# RGB_SL.net
KiCad netlist of a schematic drawn in Altium Designer
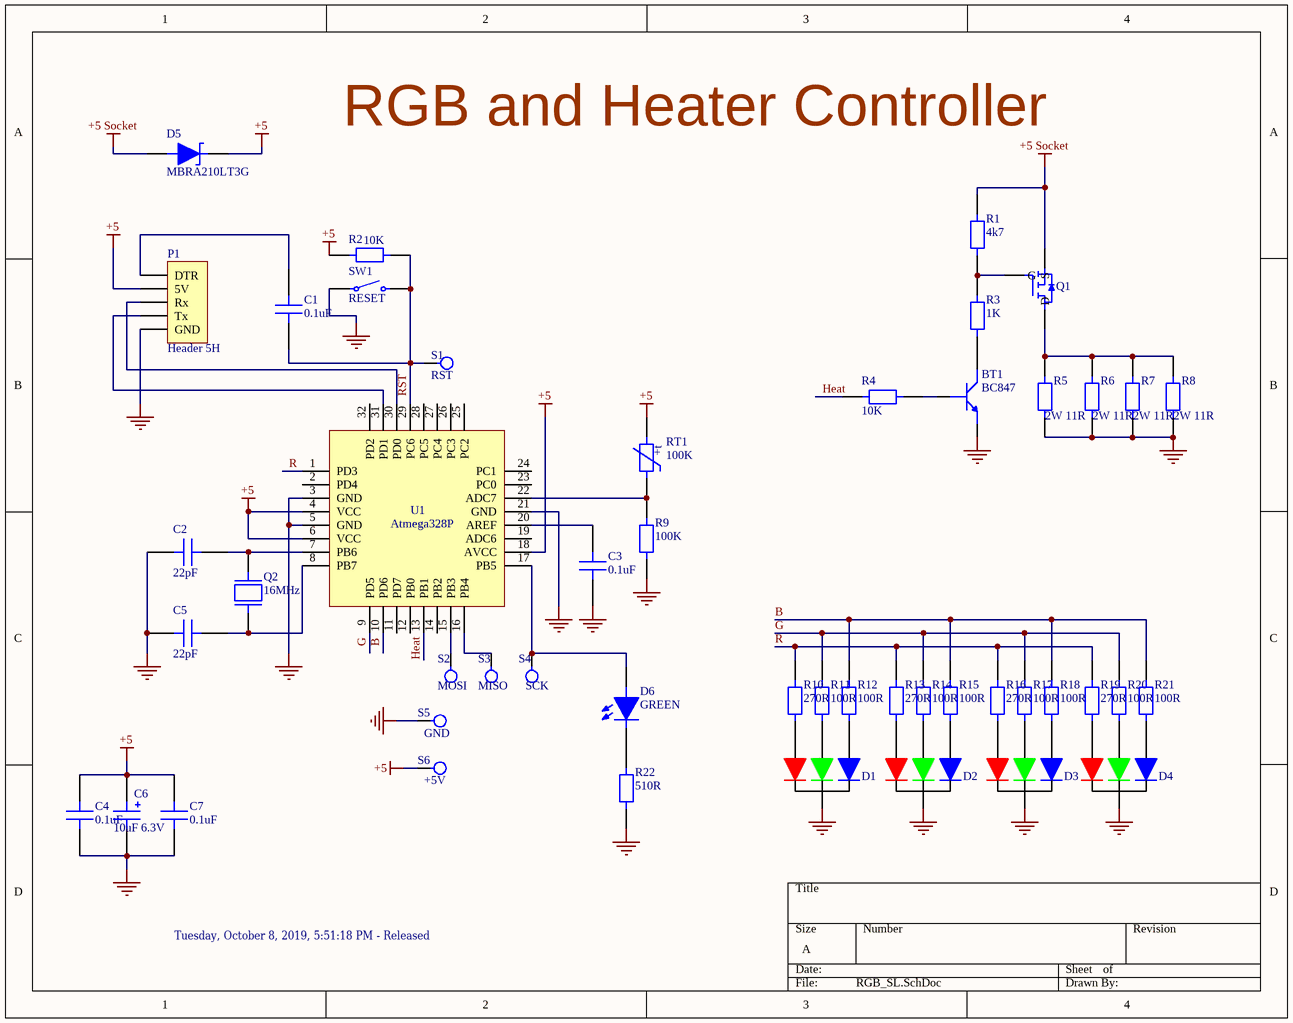
[diagram p0: RGB_SL.SchDoc]

(export (version "E")
  (design (tool "Eeschema 10.0.6"))
  (components
    (comp (ref "BT1")
      (value "BC847")
      (footprint "SOT95P240X100-3M")
      (description "Trans NPN 45V 0.1A Automotive 3-Pin SOT-23 T/R GP BJT")
      (fields
        (field (name "MANUFACTURER") "Infineon")
        (field (name "MANUFACTURER PART NUMBER") "BC847AE6327")
      )
      (libsource (lib "MainBLib") (part "BC847AE6327"))
    )
    (comp (ref "C1")
      (value "0.1uF")
      (footprint "0805 Ceramic Capacitor")
      (description "Ceramic Cap 0.1uF 50 V 10% MLCC - SMD/SMT")
      (fields
        (field (name "MANUFACTURER") "Vishay Vitramon")
        (field (name "MANUFACTURER PART NUMBER") "VJ0805Y104KXAAT")
      )
      (libsource (lib "MainBLib") (part "VJ0805Y104KXAAT"))
    )
    (comp (ref "C2")
      (value "22pF")
      (footprint "0805 Ceramic Capacitor")
      (description "Ceramic Cap 22 pF 50 V ±5 % Tolerance C0G/NP0 SMT Multilayer")
      (fields
        (field (name "MANUFACTURER") "Vishay")
        (field (name "MANUFACTURER PART NUMBER") "VJ0805A220JXACW1BC")
      )
      (libsource (lib "MainBLib") (part "VJ0805A220JXACW1BC"))
    )
    (comp (ref "C3")
      (value "0.1uF")
      (footprint "0805 Ceramic Capacitor")
      (description "Ceramic Cap 0.1uF 50 V 10% MLCC - SMD/SMT")
      (fields
        (field (name "MANUFACTURER") "Vishay Vitramon")
        (field (name "MANUFACTURER PART NUMBER") "VJ0805Y104KXAAT")
      )
      (libsource (lib "MainBLib") (part "VJ0805Y104KXAAT"))
    )
    (comp (ref "C4")
      (value "0.1uF")
      (footprint "0805 Ceramic Capacitor")
      (description "Ceramic Cap 0.1uF 50 V 10% MLCC - SMD/SMT")
      (fields
        (field (name "MANUFACTURER") "Vishay Vitramon")
        (field (name "MANUFACTURER PART NUMBER") "VJ0805Y104KXAAT")
      )
      (libsource (lib "MainBLib") (part "VJ0805Y104KXAAT"))
    )
    (comp (ref "C5")
      (value "22pF")
      (footprint "0805 Ceramic Capacitor")
      (description "Ceramic Cap 22 pF 50 V ±5 % Tolerance C0G/NP0 SMT Multilayer")
      (fields
        (field (name "MANUFACTURER") "Vishay")
        (field (name "MANUFACTURER PART NUMBER") "VJ0805A220JXACW1BC")
      )
      (libsource (lib "MainBLib") (part "VJ0805A220JXACW1BC"))
    )
    (comp (ref "C6")
      (value "10uF 6.3V")
      (footprint "CAP MP3216X16M")
      (description "CAP TANT 10UF 6.3V 10% 1206")
      (fields
        (field (name "MANUFACTURER") "Vishay Sprague")
        (field (name "MANUFACTURER PART NUMBER") "293D106X96R3A2TE3")
      )
      (libsource (lib "MainBLib") (part "293D106X96R3A2TE3"))
    )
    (comp (ref "C7")
      (value "0.1uF")
      (footprint "0805 Ceramic Capacitor")
      (description "Ceramic Cap 0.1uF 50 V 10% MLCC - SMD/SMT")
      (fields
        (field (name "MANUFACTURER") "Vishay Vitramon")
        (field (name "MANUFACTURER PART NUMBER") "VJ0805Y104KXAAT")
      )
      (libsource (lib "MainBLib") (part "VJ0805Y104KXAAT"))
    )
    (comp (ref "D1")
      (value "LED RGB")
      (footprint "LED RGB")
      (description "LED RGB DIFFUSED 5MM T/H")
      (fields (field (name "MANUFACTURER") "Inolux") (field (name "MANUFACTURER PART NUMBER") "HV-5RGB25"))
      (libsource (lib "MainBLib") (part "HV-5RGB25"))
    )
    (comp (ref "D2")
      (value "LED RGB")
      (footprint "LED RGB")
      (description "LED RGB DIFFUSED 5MM T/H")
      (fields (field (name "MANUFACTURER") "Inolux") (field (name "MANUFACTURER PART NUMBER") "HV-5RGB25"))
      (libsource (lib "MainBLib") (part "HV-5RGB25"))
    )
    (comp (ref "D3")
      (value "LED RGB")
      (footprint "LED RGB")
      (description "LED RGB DIFFUSED 5MM T/H")
      (fields (field (name "MANUFACTURER") "Inolux") (field (name "MANUFACTURER PART NUMBER") "HV-5RGB25"))
      (libsource (lib "MainBLib") (part "HV-5RGB25"))
    )
    (comp (ref "D4")
      (value "LED RGB")
      (footprint "LED RGB")
      (description "LED RGB DIFFUSED 5MM T/H")
      (fields (field (name "MANUFACTURER") "Inolux") (field (name "MANUFACTURER PART NUMBER") "HV-5RGB25"))
      (libsource (lib "MainBLib") (part "HV-5RGB25"))
    )
    (comp (ref "D5")
      (value "MBRA210LT3G")
      (footprint "DIOM4326X22M")
      (description "DIODE SCHOTTKY 10V 2A SMA")
      (fields (field (name "MANUFACTURER") "ON Semiconductor"))
      (libsource (lib "MainBLib") (part "MBRA210LT3G"))
    )
    (comp (ref "D6")
      (value "GREEN")
      (footprint "Led G")
      (description "LED GREEN DIFFUSED 0805 SMD")
      (fields
        (field (name "MANUFACTURER") "VCC CHML")
        (field (name "MANUFACTURER PART NUMBER") "CMD17-21VGD/TR8")
      )
      (libsource (lib "MainBLib") (part "CMD17-21VGD/TR8"))
    )
    (comp (ref "P1")
      (value "Header 5H")
      (footprint "HDR1X5H")
      (description "Header, 5-Pin, Right Angle")
      (fields (field (name "PUBLISHER") "Altium Limited"))
      (libsource (lib "Miscellaneous Connectors") (part "Header 5H"))
    )
    (comp (ref "Q1")
      (value "MOSFET P-Ch")
      (footprint "DPAK254P1524X483-3M")
      (description "MOSFET P-Ch LL FET Enhancement Mode")
      (fields
        (field (name "MANUFACTURER") "ON Semiconductor / Fairchild")
        (field (name "MANUFACTURER PART NUMBER") "NDP6020P")
      )
      (libsource (lib "MainBLib") (part "NDP6020P"))
    )
    (comp (ref "Q2")
      (value "16MHz")
      (footprint "Crystal")
      (description "CRYSTAL 16.0000MHZ 20PF SMD")
      (fields
        (field (name "MANUFACTURER") "ECS International")
        (field (name "MANUFACTURER PART NUMBER") "ECS-160-20-5PX-TR")
      )
      (libsource (lib "MainBLib") (part "ECS-160-20-5PX-TR"))
    )
    (comp (ref "R1")
      (value "4k7")
      (footprint "0805 Res")
      (description "RES SMD 4.7K Ohm 5% 1/8W ±200ppm/°C Molded SMD Paper T/R")
      (fields
        (field (name "MANUFACTURER") "Vishay")
        (field (name "MANUFACTURER PART NUMBER") "CRCW08054K70JNEAC")
      )
      (libsource (lib "MainBLib") (part "CRCW08054K70JNEAC"))
    )
    (comp (ref "R2")
      (value "10K")
      (footprint "0805 Res")
      (description "RES SMD 10K OHM 1% 1/8W 0805")
      (fields
        (field (name "MANUFACTURER") "Vishay Dale")
        (field (name "MANUFACTURER PART NUMBER") "CRCW080510K0FKTA")
      )
      (libsource (lib "MainBLib") (part "CRCW080510K0FKTA"))
    )
    (comp (ref "R3")
      (value "1K")
      (footprint "0805 Res")
      (description "RES SMD 1K OHM 1% 1/8W 0805")
      (fields
        (field (name "MANUFACTURER") "Vishay Dale")
        (field (name "MANUFACTURER PART NUMBER") "CRCW08051K00FKEA")
      )
      (libsource (lib "MainBLib") (part "CRCW08051K00FKEA"))
    )
    (comp (ref "R4")
      (value "10K")
      (footprint "0805 Res")
      (description "RES SMD 10K OHM 1% 1/8W 0805")
      (fields
        (field (name "MANUFACTURER") "Vishay Dale")
        (field (name "MANUFACTURER PART NUMBER") "CRCW080510K0FKTA")
      )
      (libsource (lib "MainBLib") (part "CRCW080510K0FKTA"))
    )
    (comp (ref "R5")
      (value "2W 11R")
      (footprint "RES T/H 2W")
      (description "RES T/H 11 Ohm 2W 5% ±300ppm/°C Conformal AXL Thru-Hole Ammo Pack")
      (fields
        (field (name "MANUFACTURER") "TE Connectivity")
        (field (name "MANUFACTURER PART NUMBER") "RR02J11RTB")
      )
      (libsource (lib "MainBLib") (part "RR02J11RTB"))
    )
    (comp (ref "R6")
      (value "2W 11R")
      (footprint "RES T/H 2W")
      (description "RES T/H 11 Ohm 2W 5% ±300ppm/°C Conformal AXL Thru-Hole Ammo Pack")
      (fields
        (field (name "MANUFACTURER") "TE Connectivity")
        (field (name "MANUFACTURER PART NUMBER") "RR02J11RTB")
      )
      (libsource (lib "MainBLib") (part "RR02J11RTB"))
    )
    (comp (ref "R7")
      (value "2W 11R")
      (footprint "RES T/H 2W")
      (description "RES T/H 11 Ohm 2W 5% ±300ppm/°C Conformal AXL Thru-Hole Ammo Pack")
      (fields
        (field (name "MANUFACTURER") "TE Connectivity")
        (field (name "MANUFACTURER PART NUMBER") "RR02J11RTB")
      )
      (libsource (lib "MainBLib") (part "RR02J11RTB"))
    )
    (comp (ref "R8")
      (value "2W 11R")
      (footprint "RES T/H 2W")
      (description "RES T/H 11 Ohm 2W 5% ±300ppm/°C Conformal AXL Thru-Hole Ammo Pack")
      (fields
        (field (name "MANUFACTURER") "TE Connectivity")
        (field (name "MANUFACTURER PART NUMBER") "RR02J11RTB")
      )
      (libsource (lib "MainBLib") (part "RR02J11RTB"))
    )
    (comp (ref "R9")
      (value "100K")
      (footprint "0805 Res")
      (fields
        (field (name "MANUFACTURER") "Vishay")
        (field (name "MANUFACTURER PART NUMBER") "TNPW0805100KFEEA")
        (field (name "TOLERANCE") "1%")
      )
      (libsource (lib "MainBLib") (part "TNPW0805100KFEEA"))
    )
    (comp (ref "R10")
      (value "270R")
      (footprint "1206 RES")
      (description "RES SMD 270 OHM 1% 1/4W 1206")
      (fields
        (field (name "MANUFACTURER") "Vishay Semiconductors")
        (field (name "MANUFACTURER PART NUMBER") "CRCW1206270RFKEAC")
      )
      (libsource (lib "MainBLib") (part "CRCW1206270RFKEAC"))
    )
    (comp (ref "R11")
      (value "100R")
      (footprint "1206 RES")
      (description "RES SMD 100 OHM 1% 1/4W 1206")
      (fields
        (field (name "MANUFACTURER") "Vishay Semiconductors")
        (field (name "MANUFACTURER PART NUMBER") "CRCW1206100RFKEAC")
      )
      (libsource (lib "MainBLib") (part "CRCW1206100RFKEAC"))
    )
    (comp (ref "R12")
      (value "100R")
      (footprint "1206 RES")
      (description "RES SMD 100 OHM 1% 1/4W 1206")
      (fields
        (field (name "MANUFACTURER") "Vishay Semiconductors")
        (field (name "MANUFACTURER PART NUMBER") "CRCW1206100RFKEAC")
      )
      (libsource (lib "MainBLib") (part "CRCW1206100RFKEAC"))
    )
    (comp (ref "R13")
      (value "270R")
      (footprint "1206 RES")
      (description "RES SMD 270 OHM 1% 1/4W 1206")
      (fields
        (field (name "MANUFACTURER") "Vishay Semiconductors")
        (field (name "MANUFACTURER PART NUMBER") "CRCW1206270RFKEAC")
      )
      (libsource (lib "MainBLib") (part "CRCW1206270RFKEAC"))
    )
    (comp (ref "R14")
      (value "100R")
      (footprint "1206 RES")
      (description "RES SMD 100 OHM 1% 1/4W 1206")
      (fields
        (field (name "MANUFACTURER") "Vishay Semiconductors")
        (field (name "MANUFACTURER PART NUMBER") "CRCW1206100RFKEAC")
      )
      (libsource (lib "MainBLib") (part "CRCW1206100RFKEAC"))
    )
    (comp (ref "R15")
      (value "100R")
      (footprint "1206 RES")
      (description "RES SMD 100 OHM 1% 1/4W 1206")
      (fields
        (field (name "MANUFACTURER") "Vishay Semiconductors")
        (field (name "MANUFACTURER PART NUMBER") "CRCW1206100RFKEAC")
      )
      (libsource (lib "MainBLib") (part "CRCW1206100RFKEAC"))
    )
    (comp (ref "R16")
      (value "270R")
      (footprint "1206 RES")
      (description "RES SMD 270 OHM 1% 1/4W 1206")
      (fields
        (field (name "MANUFACTURER") "Vishay Semiconductors")
        (field (name "MANUFACTURER PART NUMBER") "CRCW1206270RFKEAC")
      )
      (libsource (lib "MainBLib") (part "CRCW1206270RFKEAC"))
    )
    (comp (ref "R17")
      (value "100R")
      (footprint "1206 RES")
      (description "RES SMD 100 OHM 1% 1/4W 1206")
      (fields
        (field (name "MANUFACTURER") "Vishay Semiconductors")
        (field (name "MANUFACTURER PART NUMBER") "CRCW1206100RFKEAC")
      )
      (libsource (lib "MainBLib") (part "CRCW1206100RFKEAC"))
    )
    (comp (ref "R18")
      (value "100R")
      (footprint "1206 RES")
      (description "RES SMD 100 OHM 1% 1/4W 1206")
      (fields
        (field (name "MANUFACTURER") "Vishay Semiconductors")
        (field (name "MANUFACTURER PART NUMBER") "CRCW1206100RFKEAC")
      )
      (libsource (lib "MainBLib") (part "CRCW1206100RFKEAC"))
    )
    (comp (ref "R19")
      (value "270R")
      (footprint "1206 RES")
      (description "RES SMD 270 OHM 1% 1/4W 1206")
      (fields
        (field (name "MANUFACTURER") "Vishay Semiconductors")
        (field (name "MANUFACTURER PART NUMBER") "CRCW1206270RFKEAC")
      )
      (libsource (lib "MainBLib") (part "CRCW1206270RFKEAC"))
    )
    (comp (ref "R20")
      (value "100R")
      (footprint "1206 RES")
      (description "RES SMD 100 OHM 1% 1/4W 1206")
      (fields
        (field (name "MANUFACTURER") "Vishay Semiconductors")
        (field (name "MANUFACTURER PART NUMBER") "CRCW1206100RFKEAC")
      )
      (libsource (lib "MainBLib") (part "CRCW1206100RFKEAC"))
    )
    (comp (ref "R21")
      (value "100R")
      (footprint "1206 RES")
      (description "RES SMD 100 OHM 1% 1/4W 1206")
      (fields
        (field (name "MANUFACTURER") "Vishay Semiconductors")
        (field (name "MANUFACTURER PART NUMBER") "CRCW1206100RFKEAC")
      )
      (libsource (lib "MainBLib") (part "CRCW1206100RFKEAC"))
    )
    (comp (ref "R22")
      (value "510R")
      (footprint "0805 Res")
      (description "RES SMD 510 OHM 1% 1/8W 0805")
      (fields
        (field (name "MANUFACTURER") "Vishay")
        (field (name "MANUFACTURER PART NUMBER") "CRCW0805510RFKEA")
      )
      (libsource (lib "MainBLib") (part "CRCW0805510RFKEA"))
    )
    (comp (ref "RT1")
      (value "100K")
      (footprint "THERMISTOR")
      (description "THERMISTOR 100K OHM 5% BEAD")
      (fields
        (field (name "MANUFACTURER") "Canadian Thermostats")
        (field (name "MANUFACTURER PART NUMBER") "MF52A1104J3950")
      )
      (libsource (lib "MainBLib") (part "MF52A1104J3950"))
    )
    (comp (ref "S1") (value "RST") (footprint "Test Pad") (libsource (lib "MainBLib") (part "Test Pad")))
    (comp (ref "S2") (value "MOSI") (footprint "Test Pad") (libsource (lib "MainBLib") (part "Test Pad")))
    (comp (ref "S3") (value "MISO") (footprint "Test Pad") (libsource (lib "MainBLib") (part "Test Pad")))
    (comp (ref "S4") (value "SCK") (footprint "Test Pad") (libsource (lib "MainBLib") (part "Test Pad")))
    (comp (ref "S5") (value "GND") (footprint "Test Pad") (libsource (lib "MainBLib") (part "Test Pad")))
    (comp (ref "S6") (value "+5V") (footprint "Test Pad") (libsource (lib "MainBLib") (part "Test Pad")))
    (comp (ref "SW1")
      (value "RESET")
      (footprint "SWITCH")
      (description "SWITCH TACTILE SPST-NO 0.05A 24V")
      (fields
        (field (name "MANUFACTURER") "TE Connectivity")
        (field (name "MANUFACTURER PART NUMBER") "FSMSMTR")
      )
      (libsource (lib "MainBLib") (part "FSMSMTR"))
    )
    (comp (ref "U1")
      (value "Atmega328P")
      (footprint "TQFP80P900X900X120-32M")
      (description "IC MCU 8BIT 32KB FLASH 32TQFP")
      (fields
        (field (name "MANUFACTURER") "Microchip")
        (field (name "MANUFACTURER PART NUMBER") "ATMEGA328P-AUR")
      )
      (libsource (lib "MainBLib") (part "ATMEGA328P-AUR"))
    )
  )
  (nets
    (net (code "1") (name "+5") (class "Default")
      (node (ref "C4") (pin "2") (pinfunction "2_2") (pintype "passive"))
      (node (ref "C6") (pin "1") (pinfunction "1_1") (pintype "passive"))
      (node (ref "C7") (pin "2") (pinfunction "2_2") (pintype "passive"))
      (node (ref "D5") (pin "1") (pinfunction "1_1") (pintype "passive"))
      (node (ref "P1") (pin "2") (pinfunction "5V_2") (pintype "passive"))
      (node (ref "R2") (pin "1") (pinfunction "1_1") (pintype "passive"))
      (node (ref "RT1") (pin "2") (pinfunction "2_2") (pintype "passive"))
      (node (ref "S6") (pin "1") (pinfunction "1_1") (pintype "passive"))
      (node (ref "U1") (pin "18") (pinfunction "AVCC_18") (pintype "passive"))
      (node (ref "U1") (pin "4") (pinfunction "VCC_4") (pintype "passive"))
      (node (ref "U1") (pin "6") (pinfunction "VCC_6") (pintype "passive"))
    )
    (net (code "2") (name "+5 Socket") (class "Default")
      (node (ref "D5") (pin "2") (pinfunction "2_2") (pintype "passive"))
      (node (ref "Q1") (pin "3") (pinfunction "S_3") (pintype "passive"))
      (node (ref "R1") (pin "2") (pinfunction "2_2") (pintype "passive"))
    )
    (net (code "3") (name "/B") (class "Default")
      (node (ref "R12") (pin "2") (pinfunction "2_2") (pintype "passive"))
      (node (ref "R15") (pin "2") (pinfunction "2_2") (pintype "passive"))
      (node (ref "R18") (pin "2") (pinfunction "2_2") (pintype "passive"))
      (node (ref "R21") (pin "2") (pinfunction "2_2") (pintype "passive"))
      (node (ref "U1") (pin "10") (pinfunction "PD6_10") (pintype "passive"))
    )
    (net (code "4") (name "/G") (class "Default")
      (node (ref "R11") (pin "2") (pinfunction "2_2") (pintype "passive"))
      (node (ref "R14") (pin "2") (pinfunction "2_2") (pintype "passive"))
      (node (ref "R17") (pin "2") (pinfunction "2_2") (pintype "passive"))
      (node (ref "R20") (pin "2") (pinfunction "2_2") (pintype "passive"))
      (node (ref "U1") (pin "9") (pinfunction "PD5_9") (pintype "passive"))
    )
    (net (code "5") (name "/Heat") (class "Default")
      (node (ref "R4") (pin "1") (pinfunction "1_1") (pintype "passive"))
      (node (ref "U1") (pin "13") (pinfunction "PB1_13") (pintype "passive"))
    )
    (net (code "6") (name "/R") (class "Default")
      (node (ref "R10") (pin "2") (pinfunction "2_2") (pintype "passive"))
      (node (ref "R13") (pin "2") (pinfunction "2_2") (pintype "passive"))
      (node (ref "R16") (pin "2") (pinfunction "2_2") (pintype "passive"))
      (node (ref "R19") (pin "2") (pinfunction "2_2") (pintype "passive"))
      (node (ref "U1") (pin "1") (pinfunction "PD3_1") (pintype "passive"))
    )
    (net (code "7") (name "/RST") (class "Default")
      (node (ref "C1") (pin "1") (pinfunction "1_1") (pintype "passive"))
      (node (ref "R2") (pin "2") (pinfunction "2_2") (pintype "passive"))
      (node (ref "S1") (pin "1") (pinfunction "1_1") (pintype "passive"))
      (node (ref "SW1") (pin "2") (pinfunction "2_2") (pintype "passive"))
      (node (ref "U1") (pin "29") (pinfunction "PC6_29") (pintype "passive"))
    )
    (net (code "8") (name "GND") (class "Default")
      (node (ref "BT1") (pin "2") (pinfunction "2_2") (pintype "passive"))
      (node (ref "C2") (pin "1") (pinfunction "1_1") (pintype "passive"))
      (node (ref "C3") (pin "1") (pinfunction "1_1") (pintype "passive"))
      (node (ref "C4") (pin "1") (pinfunction "1_1") (pintype "passive"))
      (node (ref "C5") (pin "1") (pinfunction "1_1") (pintype "passive"))
      (node (ref "C6") (pin "2") (pinfunction "2_2") (pintype "passive"))
      (node (ref "C7") (pin "1") (pinfunction "1_1") (pintype "passive"))
      (node (ref "D1") (pin "3") (pinfunction "3_3") (pintype "passive"))
      (node (ref "D2") (pin "3") (pinfunction "3_3") (pintype "passive"))
      (node (ref "D3") (pin "3") (pinfunction "3_3") (pintype "passive"))
      (node (ref "D4") (pin "3") (pinfunction "3_3") (pintype "passive"))
      (node (ref "P1") (pin "5") (pinfunction "GND_5") (pintype "passive"))
      (node (ref "R22") (pin "1") (pinfunction "1_1") (pintype "passive"))
      (node (ref "R5") (pin "1") (pinfunction "1_1") (pintype "passive"))
      (node (ref "R6") (pin "1") (pinfunction "1_1") (pintype "passive"))
      (node (ref "R7") (pin "1") (pinfunction "1_1") (pintype "passive"))
      (node (ref "R8") (pin "1") (pinfunction "1_1") (pintype "passive"))
      (node (ref "R9") (pin "1") (pinfunction "1_1") (pintype "passive"))
      (node (ref "S5") (pin "1") (pinfunction "1_1") (pintype "passive"))
      (node (ref "SW1") (pin "1") (pinfunction "1_1") (pintype "passive"))
      (node (ref "U1") (pin "21") (pinfunction "GND_21") (pintype "passive"))
      (node (ref "U1") (pin "3") (pinfunction "GND_3") (pintype "passive"))
      (node (ref "U1") (pin "5") (pinfunction "GND_5") (pintype "passive"))
    )
    (net (code "9") (name "Net-(BT1-Pad1)") (class "Default")
      (node (ref "BT1") (pin "1") (pinfunction "1_1") (pintype "passive"))
      (node (ref "R4") (pin "2") (pinfunction "2_2") (pintype "passive"))
    )
    (net (code "10") (name "Net-(BT1-Pad3)") (class "Default")
      (node (ref "BT1") (pin "3") (pinfunction "3_3") (pintype "passive"))
      (node (ref "R3") (pin "1") (pinfunction "1_1") (pintype "passive"))
    )
    (net (code "11") (name "Net-(D1-B)") (class "Default")
      (node (ref "D1") (pin "1") (pinfunction "B_1") (pintype "passive"))
      (node (ref "R12") (pin "1") (pinfunction "1_1") (pintype "passive"))
    )
    (net (code "12") (name "Net-(D1-G)") (class "Default")
      (node (ref "D1") (pin "4") (pinfunction "G_4") (pintype "passive"))
      (node (ref "R11") (pin "1") (pinfunction "1_1") (pintype "passive"))
    )
    (net (code "13") (name "Net-(D1-R)") (class "Default")
      (node (ref "D1") (pin "2") (pinfunction "R_2") (pintype "passive"))
      (node (ref "R10") (pin "1") (pinfunction "1_1") (pintype "passive"))
    )
    (net (code "14") (name "Net-(D2-B)") (class "Default")
      (node (ref "D2") (pin "1") (pinfunction "B_1") (pintype "passive"))
      (node (ref "R15") (pin "1") (pinfunction "1_1") (pintype "passive"))
    )
    (net (code "15") (name "Net-(D2-G)") (class "Default")
      (node (ref "D2") (pin "4") (pinfunction "G_4") (pintype "passive"))
      (node (ref "R14") (pin "1") (pinfunction "1_1") (pintype "passive"))
    )
    (net (code "16") (name "Net-(D2-R)") (class "Default")
      (node (ref "D2") (pin "2") (pinfunction "R_2") (pintype "passive"))
      (node (ref "R13") (pin "1") (pinfunction "1_1") (pintype "passive"))
    )
    (net (code "17") (name "Net-(D3-B)") (class "Default")
      (node (ref "D3") (pin "1") (pinfunction "B_1") (pintype "passive"))
      (node (ref "R18") (pin "1") (pinfunction "1_1") (pintype "passive"))
    )
    (net (code "18") (name "Net-(D3-G)") (class "Default")
      (node (ref "D3") (pin "4") (pinfunction "G_4") (pintype "passive"))
      (node (ref "R17") (pin "1") (pinfunction "1_1") (pintype "passive"))
    )
    (net (code "19") (name "Net-(D3-R)") (class "Default")
      (node (ref "D3") (pin "2") (pinfunction "R_2") (pintype "passive"))
      (node (ref "R16") (pin "1") (pinfunction "1_1") (pintype "passive"))
    )
    (net (code "20") (name "Net-(D4-B)") (class "Default")
      (node (ref "D4") (pin "1") (pinfunction "B_1") (pintype "passive"))
      (node (ref "R21") (pin "1") (pinfunction "1_1") (pintype "passive"))
    )
    (net (code "21") (name "Net-(D4-G)") (class "Default")
      (node (ref "D4") (pin "4") (pinfunction "G_4") (pintype "passive"))
      (node (ref "R20") (pin "1") (pinfunction "1_1") (pintype "passive"))
    )
    (net (code "22") (name "Net-(D4-R)") (class "Default")
      (node (ref "D4") (pin "2") (pinfunction "R_2") (pintype "passive"))
      (node (ref "R19") (pin "1") (pinfunction "1_1") (pintype "passive"))
    )
    (net (code "23") (name "Net-(D6-Pad2)") (class "Default")
      (node (ref "D6") (pin "2") (pinfunction "2_2") (pintype "passive"))
      (node (ref "R22") (pin "2") (pinfunction "2_2") (pintype "passive"))
    )
    (net (code "24") (name "Net-(P1-DTR)") (class "Default")
      (node (ref "C1") (pin "2") (pinfunction "2_2") (pintype "passive"))
      (node (ref "P1") (pin "1") (pinfunction "DTR_1") (pintype "passive"))
    )
    (net (code "25") (name "Net-(P1-Rx)") (class "Default")
      (node (ref "P1") (pin "4") (pinfunction "Rx_4") (pintype "passive"))
      (node (ref "U1") (pin "30") (pinfunction "PD0_30") (pintype "passive"))
    )
    (net (code "26") (name "Net-(P1-Tx)") (class "Default")
      (node (ref "P1") (pin "3") (pinfunction "Tx_3") (pintype "passive"))
      (node (ref "U1") (pin "31") (pinfunction "PD1_31") (pintype "passive"))
    )
    (net (code "27") (name "Net-(Q1-D)") (class "Default")
      (node (ref "Q1") (pin "4") (pinfunction "D_4") (pintype "passive"))
      (node (ref "R5") (pin "2") (pinfunction "2_2") (pintype "passive"))
      (node (ref "R6") (pin "2") (pinfunction "2_2") (pintype "passive"))
      (node (ref "R7") (pin "2") (pinfunction "2_2") (pintype "passive"))
      (node (ref "R8") (pin "2") (pinfunction "2_2") (pintype "passive"))
    )
    (net (code "28") (name "Net-(Q1-G)") (class "Default")
      (node (ref "Q1") (pin "1") (pinfunction "G_1") (pintype "passive"))
      (node (ref "R1") (pin "1") (pinfunction "1_1") (pintype "passive"))
      (node (ref "R3") (pin "2") (pinfunction "2_2") (pintype "passive"))
    )
    (net (code "29") (name "Net-(U1-ADC7)") (class "Default")
      (node (ref "R9") (pin "2") (pinfunction "2_2") (pintype "passive"))
      (node (ref "RT1") (pin "1") (pinfunction "1_1") (pintype "passive"))
      (node (ref "U1") (pin "22") (pinfunction "ADC7_22") (pintype "passive"))
    )
    (net (code "30") (name "Net-(U1-AREF)") (class "Default")
      (node (ref "C3") (pin "2") (pinfunction "2_2") (pintype "passive"))
      (node (ref "U1") (pin "20") (pinfunction "AREF_20") (pintype "passive"))
    )
    (net (code "31") (name "Net-(U1-PB3)") (class "Default")
      (node (ref "S2") (pin "1") (pinfunction "1_1") (pintype "passive"))
      (node (ref "U1") (pin "15") (pinfunction "PB3_15") (pintype "passive"))
    )
    (net (code "32") (name "Net-(U1-PB4)") (class "Default")
      (node (ref "S3") (pin "1") (pinfunction "1_1") (pintype "passive"))
      (node (ref "U1") (pin "16") (pinfunction "PB4_16") (pintype "passive"))
    )
    (net (code "33") (name "Net-(U1-PB5)") (class "Default")
      (node (ref "D6") (pin "1") (pinfunction "1_1") (pintype "passive"))
      (node (ref "S4") (pin "1") (pinfunction "1_1") (pintype "passive"))
      (node (ref "U1") (pin "17") (pinfunction "PB5_17") (pintype "passive"))
    )
    (net (code "34") (name "Net-(U1-PB6)") (class "Default")
      (node (ref "C2") (pin "2") (pinfunction "2_2") (pintype "passive"))
      (node (ref "Q2") (pin "1") (pinfunction "1_1") (pintype "passive"))
      (node (ref "U1") (pin "7") (pinfunction "PB6_7") (pintype "passive"))
    )
    (net (code "35") (name "Net-(U1-PB7)") (class "Default")
      (node (ref "C5") (pin "2") (pinfunction "2_2") (pintype "passive"))
      (node (ref "Q2") (pin "2") (pinfunction "2_2") (pintype "passive"))
      (node (ref "U1") (pin "8") (pinfunction "PB7_8") (pintype "passive"))
    )
    (net (code "36") (name "unconnected-(U1-ADC6-Pad19)") (class "Default")
      (node (ref "U1") (pin "19") (pinfunction "ADC6_19") (pintype "passive"))
    )
    (net (code "37") (name "unconnected-(U1-PB0-Pad12)") (class "Default")
      (node (ref "U1") (pin "12") (pinfunction "PB0_12") (pintype "passive"))
    )
    (net (code "38") (name "unconnected-(U1-PB2-Pad14)") (class "Default")
      (node (ref "U1") (pin "14") (pinfunction "PB2_14") (pintype "passive"))
    )
    (net (code "39") (name "unconnected-(U1-PC0-Pad23)") (class "Default")
      (node (ref "U1") (pin "23") (pinfunction "PC0_23") (pintype "passive"))
    )
    (net (code "40") (name "unconnected-(U1-PC1-Pad24)") (class "Default")
      (node (ref "U1") (pin "24") (pinfunction "PC1_24") (pintype "passive"))
    )
    (net (code "41") (name "unconnected-(U1-PC2-Pad25)") (class "Default")
      (node (ref "U1") (pin "25") (pinfunction "PC2_25") (pintype "passive"))
    )
    (net (code "42") (name "unconnected-(U1-PC3-Pad26)") (class "Default")
      (node (ref "U1") (pin "26") (pinfunction "PC3_26") (pintype "passive"))
    )
    (net (code "43") (name "unconnected-(U1-PC4-Pad27)") (class "Default")
      (node (ref "U1") (pin "27") (pinfunction "PC4_27") (pintype "passive"))
    )
    (net (code "44") (name "unconnected-(U1-PC5-Pad28)") (class "Default")
      (node (ref "U1") (pin "28") (pinfunction "PC5_28") (pintype "passive"))
    )
    (net (code "45") (name "unconnected-(U1-PD2-Pad32)") (class "Default")
      (node (ref "U1") (pin "32") (pinfunction "PD2_32") (pintype "passive"))
    )
    (net (code "46") (name "unconnected-(U1-PD4-Pad2)") (class "Default")
      (node (ref "U1") (pin "2") (pinfunction "PD4_2") (pintype "passive"))
    )
    (net (code "47") (name "unconnected-(U1-PD7-Pad11)") (class "Default")
      (node (ref "U1") (pin "11") (pinfunction "PD7_11") (pintype "passive"))
    )
  )
)
